# YA-S-Microcontroller-V1_0.net
KiCad netlist of a schematic drawn in Altium Designer
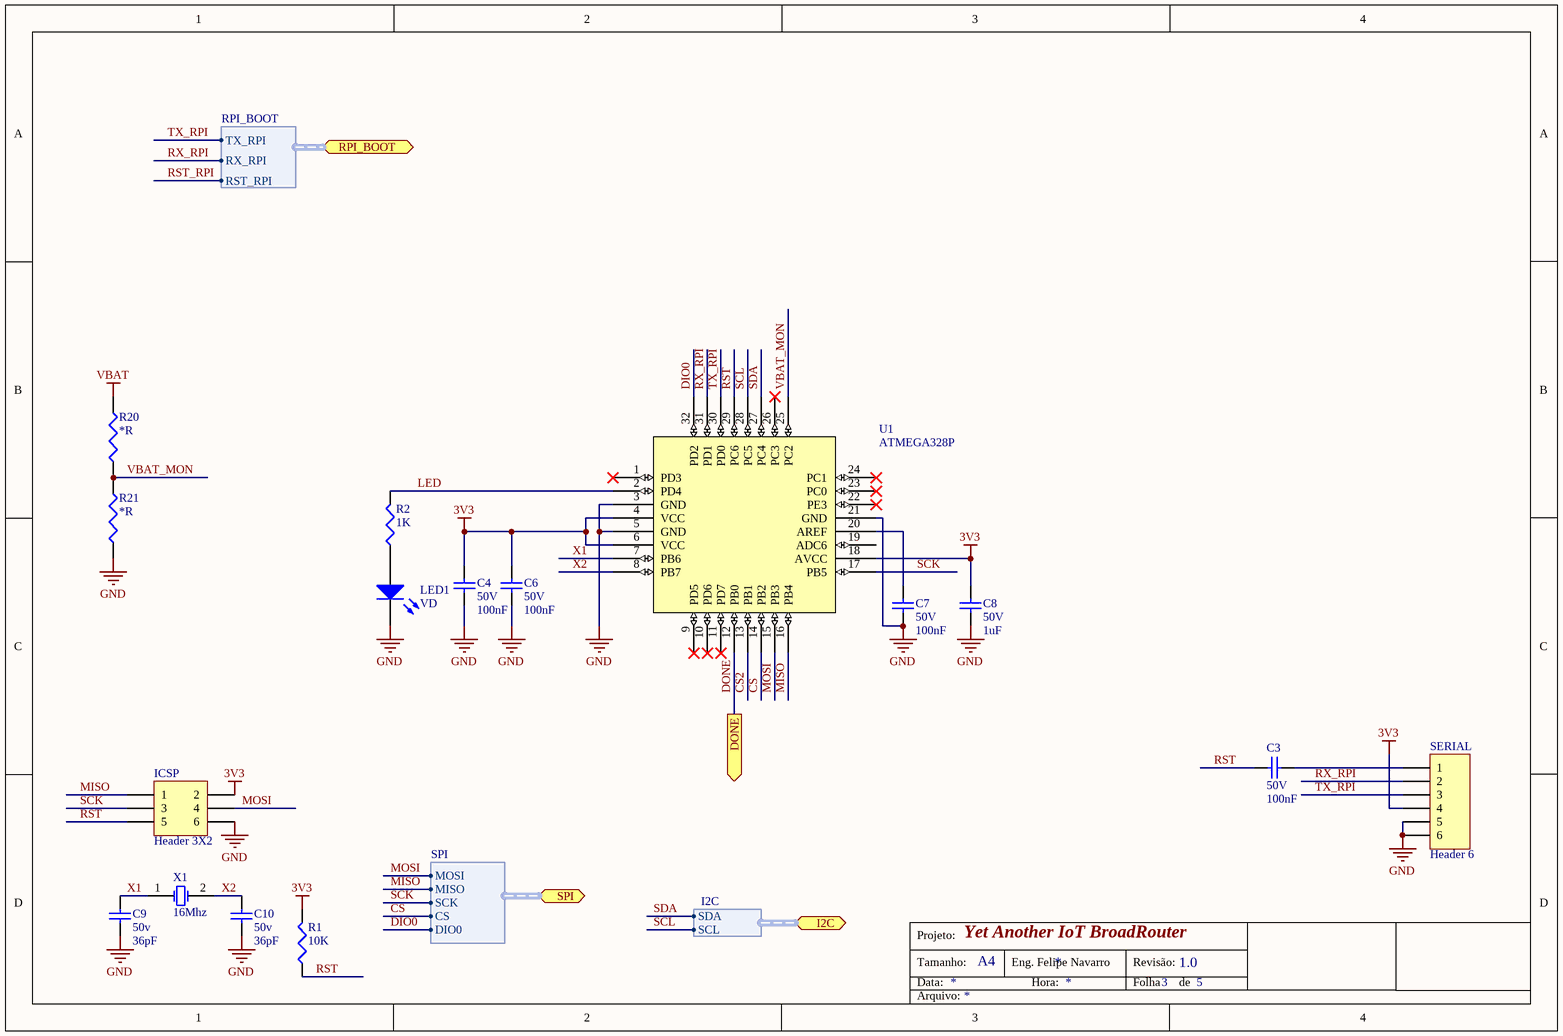
[diagram p0: YA-S-Microcontroller-V1.0.SchDoc]

(export (version "E")
  (design (tool "Eeschema 10.0.6"))
  (components
    (comp (ref "C3")
      (value "100nF")
      (footprint "CC0603")
      (description "Capacitor (Semiconductor SIM Model)")
      (fields (field (name "TENSÃO") "50V") (field (name "Comment") "Capacitor Cerâmico"))
      (libsource (lib "NavarroCAP") (part "Cap 100nF 50V 0603 X7R"))
    )
    (comp (ref "C4")
      (value "100nF")
      (footprint "CC0603")
      (description "Capacitor (Semiconductor SIM Model)")
      (fields (field (name "TENSÃO") "50V") (field (name "Comment") "Capacitor Cerâmico"))
      (libsource (lib "NavarroCAP") (part "Cap 100nF 50V 0603 X7R"))
    )
    (comp (ref "C6")
      (value "100nF")
      (footprint "CC0603")
      (description "Capacitor (Semiconductor SIM Model)")
      (fields (field (name "TENSÃO") "50V") (field (name "Comment") "Capacitor Cerâmico"))
      (libsource (lib "NavarroCAP") (part "Cap 100nF 50V 0603 X7R"))
    )
    (comp (ref "C7")
      (value "100nF")
      (footprint "CC0603")
      (description "Capacitor (Semiconductor SIM Model)")
      (fields (field (name "TENSÃO") "50V") (field (name "Comment") "Capacitor Cerâmico"))
      (libsource (lib "NavarroCAP") (part "Cap 100nF 50V 0603 X7R"))
    )
    (comp (ref "C8")
      (value "1uF")
      (footprint "CC0603")
      (description "Capacitor (Semiconductor SIM Model)")
      (fields (field (name "TENSÃO") "50V") (field (name "Comment") "Capacitor Cerâmico"))
      (libsource (lib "NavarroCAP") (part "Cap 1uF 50V 0603 X5R"))
    )
    (comp (ref "C9")
      (value "36pF")
      (footprint "CC0603")
      (description "Capacitor (Semiconductor SIM Model)")
      (fields (field (name "TENSÃO") "50v") (field (name "Comment") "Capacitor Cerâmico"))
      (libsource (lib "NavarroCAP") (part "Cap - $Val $V $Footprint $Classe_1"))
    )
    (comp (ref "C10")
      (value "36pF")
      (footprint "CC0603")
      (description "Capacitor (Semiconductor SIM Model)")
      (fields (field (name "TENSÃO") "50v") (field (name "Comment") "Capacitor Cerâmico"))
      (libsource (lib "NavarroCAP") (part "Cap - $Val $V $Footprint $Classe_1"))
    )
    (comp (ref "ICSP")
      (value "Header 3X2")
      (footprint "CONN HDR2X3")
      (description "Header, 5-Pin, Dual row")
      (libsource (lib "NavarroCON") (part "Header 3X2"))
    )
    (comp (ref "LED1")
      (value "VD")
      (footprint "LED 0603")
      (description "LED")
      (libsource (lib "NavarroSEMI") (part "LED 0603 VD 2V 75mW"))
    )
    (comp (ref "R1")
      (value "10K")
      (footprint "CC0603")
      (description "Resistor")
      (libsource (lib "NavarroRES") (part "Res 10K 1% 0603 1/10W"))
    )
    (comp (ref "R2")
      (value "1K")
      (footprint "CC0603")
      (description "Resistor")
      (libsource (lib "NavarroRES") (part "Res 1K 1% 0603 1/10W"))
    )
    (comp (ref "R20")
      (value "*R")
      (footprint "CC0603")
      (description "Resistor")
      (libsource (lib "NavarroRES") (part "Res - $Val $% $Footprint $Pot"))
    )
    (comp (ref "R21")
      (value "*R")
      (footprint "CC0603")
      (description "Resistor")
      (libsource (lib "NavarroRES") (part "Res - $Val $% $Footprint $Pot"))
    )
    (comp (ref "SERIAL")
      (value "Header 6")
      (footprint "CONN HDR1X6")
      (description "Header, 6-Pin")
      (libsource (lib "NavarroCON") (part "Header 6"))
    )
    (comp (ref "U1")
      (value "ATMEGA328P")
      (footprint "TQFP-32N")
      (description "IC MCU 32KB FLASH 20MHZ 32TQFP")
      (libsource (lib "Navarro") (part "ATMEGA328P"))
    )
    (comp (ref "X1")
      (value "16Mhz")
      (footprint "HC/49US")
      (description "Crystal Oscillator")
      (libsource (lib "Navarro") (part "XTAL"))
    )
  )
  (nets
    (net (code "4") (name "/CS") (class "Default")
      (node (ref "U1") (pin "14") (pinfunction "PB2_14") (pintype "bidirectional"))
    )
    (net (code "5") (name "/CS2") (class "Default")
      (node (ref "U1") (pin "13") (pinfunction "PB1_13") (pintype "bidirectional"))
    )
    (net (code "6") (name "/DIO0") (class "Default")
      (node (ref "U1") (pin "32") (pinfunction "PD2_32") (pintype "bidirectional"))
    )
    (net (code "7") (name "/DONE") (class "Default")
      (node (ref "U1") (pin "12") (pinfunction "PB0_12") (pintype "bidirectional"))
    )
    (net (code "8") (name "/LED") (class "Default")
      (node (ref "R2") (pin "2") (pinfunction "2_2") (pintype "passive"))
      (node (ref "U1") (pin "2") (pinfunction "PD4_2") (pintype "bidirectional"))
    )
    (net (code "9") (name "/MISO") (class "Default")
      (node (ref "ICSP") (pin "1") (pinfunction "1_1") (pintype "passive"))
      (node (ref "U1") (pin "16") (pinfunction "PB4_16") (pintype "bidirectional"))
    )
    (net (code "10") (name "/MOSI") (class "Default")
      (node (ref "ICSP") (pin "4") (pinfunction "4_4") (pintype "passive"))
      (node (ref "U1") (pin "15") (pinfunction "PB3_15") (pintype "bidirectional"))
    )
    (net (code "11") (name "/RST") (class "Default")
      (node (ref "C3") (pin "2") (pinfunction "2_2") (pintype "passive"))
      (node (ref "ICSP") (pin "5") (pinfunction "5_5") (pintype "passive"))
      (node (ref "R1") (pin "1") (pinfunction "1_1") (pintype "passive"))
      (node (ref "U1") (pin "29") (pinfunction "PC6_29") (pintype "bidirectional"))
    )
    (net (code "13") (name "/RX_RPI") (class "Default")
      (node (ref "SERIAL") (pin "2") (pinfunction "2_2") (pintype "passive"))
      (node (ref "U1") (pin "31") (pinfunction "PD1_31") (pintype "bidirectional"))
    )
    (net (code "14") (name "/SCK") (class "Default")
      (node (ref "ICSP") (pin "3") (pinfunction "3_3") (pintype "passive"))
      (node (ref "U1") (pin "17") (pinfunction "PB5_17") (pintype "bidirectional"))
    )
    (net (code "15") (name "/SCL") (class "Default")
      (node (ref "U1") (pin "28") (pinfunction "PC5_28") (pintype "bidirectional"))
    )
    (net (code "16") (name "/SDA") (class "Default")
      (node (ref "U1") (pin "27") (pinfunction "PC4_27") (pintype "bidirectional"))
    )
    (net (code "17") (name "/TX_RPI") (class "Default")
      (node (ref "SERIAL") (pin "3") (pinfunction "3_3") (pintype "passive"))
      (node (ref "U1") (pin "30") (pinfunction "PD0_30") (pintype "bidirectional"))
    )
    (net (code "18") (name "/VBAT_MON") (class "Default")
      (node (ref "R20") (pin "1") (pinfunction "1_1") (pintype "passive"))
      (node (ref "R21") (pin "2") (pinfunction "2_2") (pintype "passive"))
      (node (ref "U1") (pin "25") (pinfunction "PC2_25") (pintype "bidirectional"))
    )
    (net (code "19") (name "/X1") (class "Default")
      (node (ref "C9") (pin "2") (pinfunction "2_2") (pintype "passive"))
      (node (ref "U1") (pin "7") (pinfunction "PB6_7") (pintype "bidirectional"))
      (node (ref "X1") (pin "1") (pinfunction "OSC1_1") (pintype "passive"))
    )
    (net (code "20") (name "/X2") (class "Default")
      (node (ref "C10") (pin "2") (pinfunction "2_2") (pintype "passive"))
      (node (ref "U1") (pin "8") (pinfunction "PB7_8") (pintype "bidirectional"))
      (node (ref "X1") (pin "2") (pinfunction "OSC2_2") (pintype "passive"))
    )
    (net (code "24") (name "3V3") (class "Default")
      (node (ref "C4") (pin "2") (pinfunction "2_2") (pintype "passive"))
      (node (ref "C6") (pin "2") (pinfunction "2_2") (pintype "passive"))
      (node (ref "C8") (pin "2") (pinfunction "2_2") (pintype "passive"))
      (node (ref "ICSP") (pin "2") (pinfunction "2_2") (pintype "passive"))
      (node (ref "R1") (pin "2") (pinfunction "2_2") (pintype "passive"))
      (node (ref "SERIAL") (pin "4") (pinfunction "4_4") (pintype "passive"))
      (node (ref "U1") (pin "18") (pinfunction "AVCC_18") (pintype "power_in"))
      (node (ref "U1") (pin "4") (pinfunction "VCC_4") (pintype "power_in"))
      (node (ref "U1") (pin "6") (pinfunction "VCC_6") (pintype "power_in"))
    )
    (net (code "25") (name "GND") (class "Default")
      (node (ref "C10") (pin "1") (pinfunction "1_1") (pintype "passive"))
      (node (ref "C4") (pin "1") (pinfunction "1_1") (pintype "passive"))
      (node (ref "C6") (pin "1") (pinfunction "1_1") (pintype "passive"))
      (node (ref "C7") (pin "1") (pinfunction "1_1") (pintype "passive"))
      (node (ref "C8") (pin "1") (pinfunction "1_1") (pintype "passive"))
      (node (ref "C9") (pin "1") (pinfunction "1_1") (pintype "passive"))
      (node (ref "ICSP") (pin "6") (pinfunction "6_6") (pintype "passive"))
      (node (ref "LED1") (pin "2") (pinfunction "K_2") (pintype "passive"))
      (node (ref "R21") (pin "1") (pinfunction "1_1") (pintype "passive"))
      (node (ref "SERIAL") (pin "5") (pinfunction "5_5") (pintype "passive"))
      (node (ref "SERIAL") (pin "6") (pinfunction "6_6") (pintype "passive"))
      (node (ref "U1") (pin "21") (pinfunction "GND_21") (pintype "power_in"))
      (node (ref "U1") (pin "3") (pinfunction "GND_3") (pintype "power_in"))
      (node (ref "U1") (pin "5") (pinfunction "GND_5") (pintype "power_in"))
    )
    (net (code "26") (name "Net-(C3-Pad1)") (class "Default")
      (node (ref "C3") (pin "1") (pinfunction "1_1") (pintype "passive"))
      (node (ref "SERIAL") (pin "1") (pinfunction "1_1") (pintype "passive"))
    )
    (net (code "27") (name "Net-(LED1-A)") (class "Default")
      (node (ref "LED1") (pin "1") (pinfunction "A_1") (pintype "passive"))
      (node (ref "R2") (pin "1") (pinfunction "1_1") (pintype "passive"))
    )
    (net (code "28") (name "Net-(U1-AREF)") (class "Default")
      (node (ref "C7") (pin "2") (pinfunction "2_2") (pintype "passive"))
      (node (ref "U1") (pin "20") (pinfunction "AREF_20") (pintype "passive"))
    )
    (net (code "29") (name "VBAT") (class "Default")
      (node (ref "R20") (pin "2") (pinfunction "2_2") (pintype "passive"))
    )
    (net (code "30") (name "unconnected-(U1-ADC6-Pad19)") (class "Default")
      (node (ref "U1") (pin "19") (pinfunction "ADC6_19") (pintype "bidirectional"))
    )
    (net (code "31") (name "unconnected-(U1-PC0-Pad23)") (class "Default")
      (node (ref "U1") (pin "23") (pinfunction "PC0_23") (pintype "bidirectional+no_connect"))
    )
    (net (code "32") (name "unconnected-(U1-PC1-Pad24)") (class "Default")
      (node (ref "U1") (pin "24") (pinfunction "PC1_24") (pintype "bidirectional+no_connect"))
    )
    (net (code "33") (name "unconnected-(U1-PC3-Pad26)") (class "Default")
      (node (ref "U1") (pin "26") (pinfunction "PC3_26") (pintype "bidirectional+no_connect"))
    )
    (net (code "34") (name "unconnected-(U1-PD3-Pad1)") (class "Default")
      (node (ref "U1") (pin "1") (pinfunction "PD3_1") (pintype "bidirectional+no_connect"))
    )
    (net (code "35") (name "unconnected-(U1-PD5-Pad9)") (class "Default")
      (node (ref "U1") (pin "9") (pinfunction "PD5_9") (pintype "bidirectional+no_connect"))
    )
    (net (code "36") (name "unconnected-(U1-PD6-Pad10)") (class "Default")
      (node (ref "U1") (pin "10") (pinfunction "PD6_10") (pintype "bidirectional+no_connect"))
    )
    (net (code "37") (name "unconnected-(U1-PD7-Pad11)") (class "Default")
      (node (ref "U1") (pin "11") (pinfunction "PD7_11") (pintype "bidirectional+no_connect"))
    )
    (net (code "38") (name "unconnected-(U1-PE3-Pad22)") (class "Default")
      (node (ref "U1") (pin "22") (pinfunction "PE3_22") (pintype "bidirectional+no_connect"))
    )
  )
)
